# FPGA_GTX.net
KiCad netlist of a schematic drawn in Altium Designer
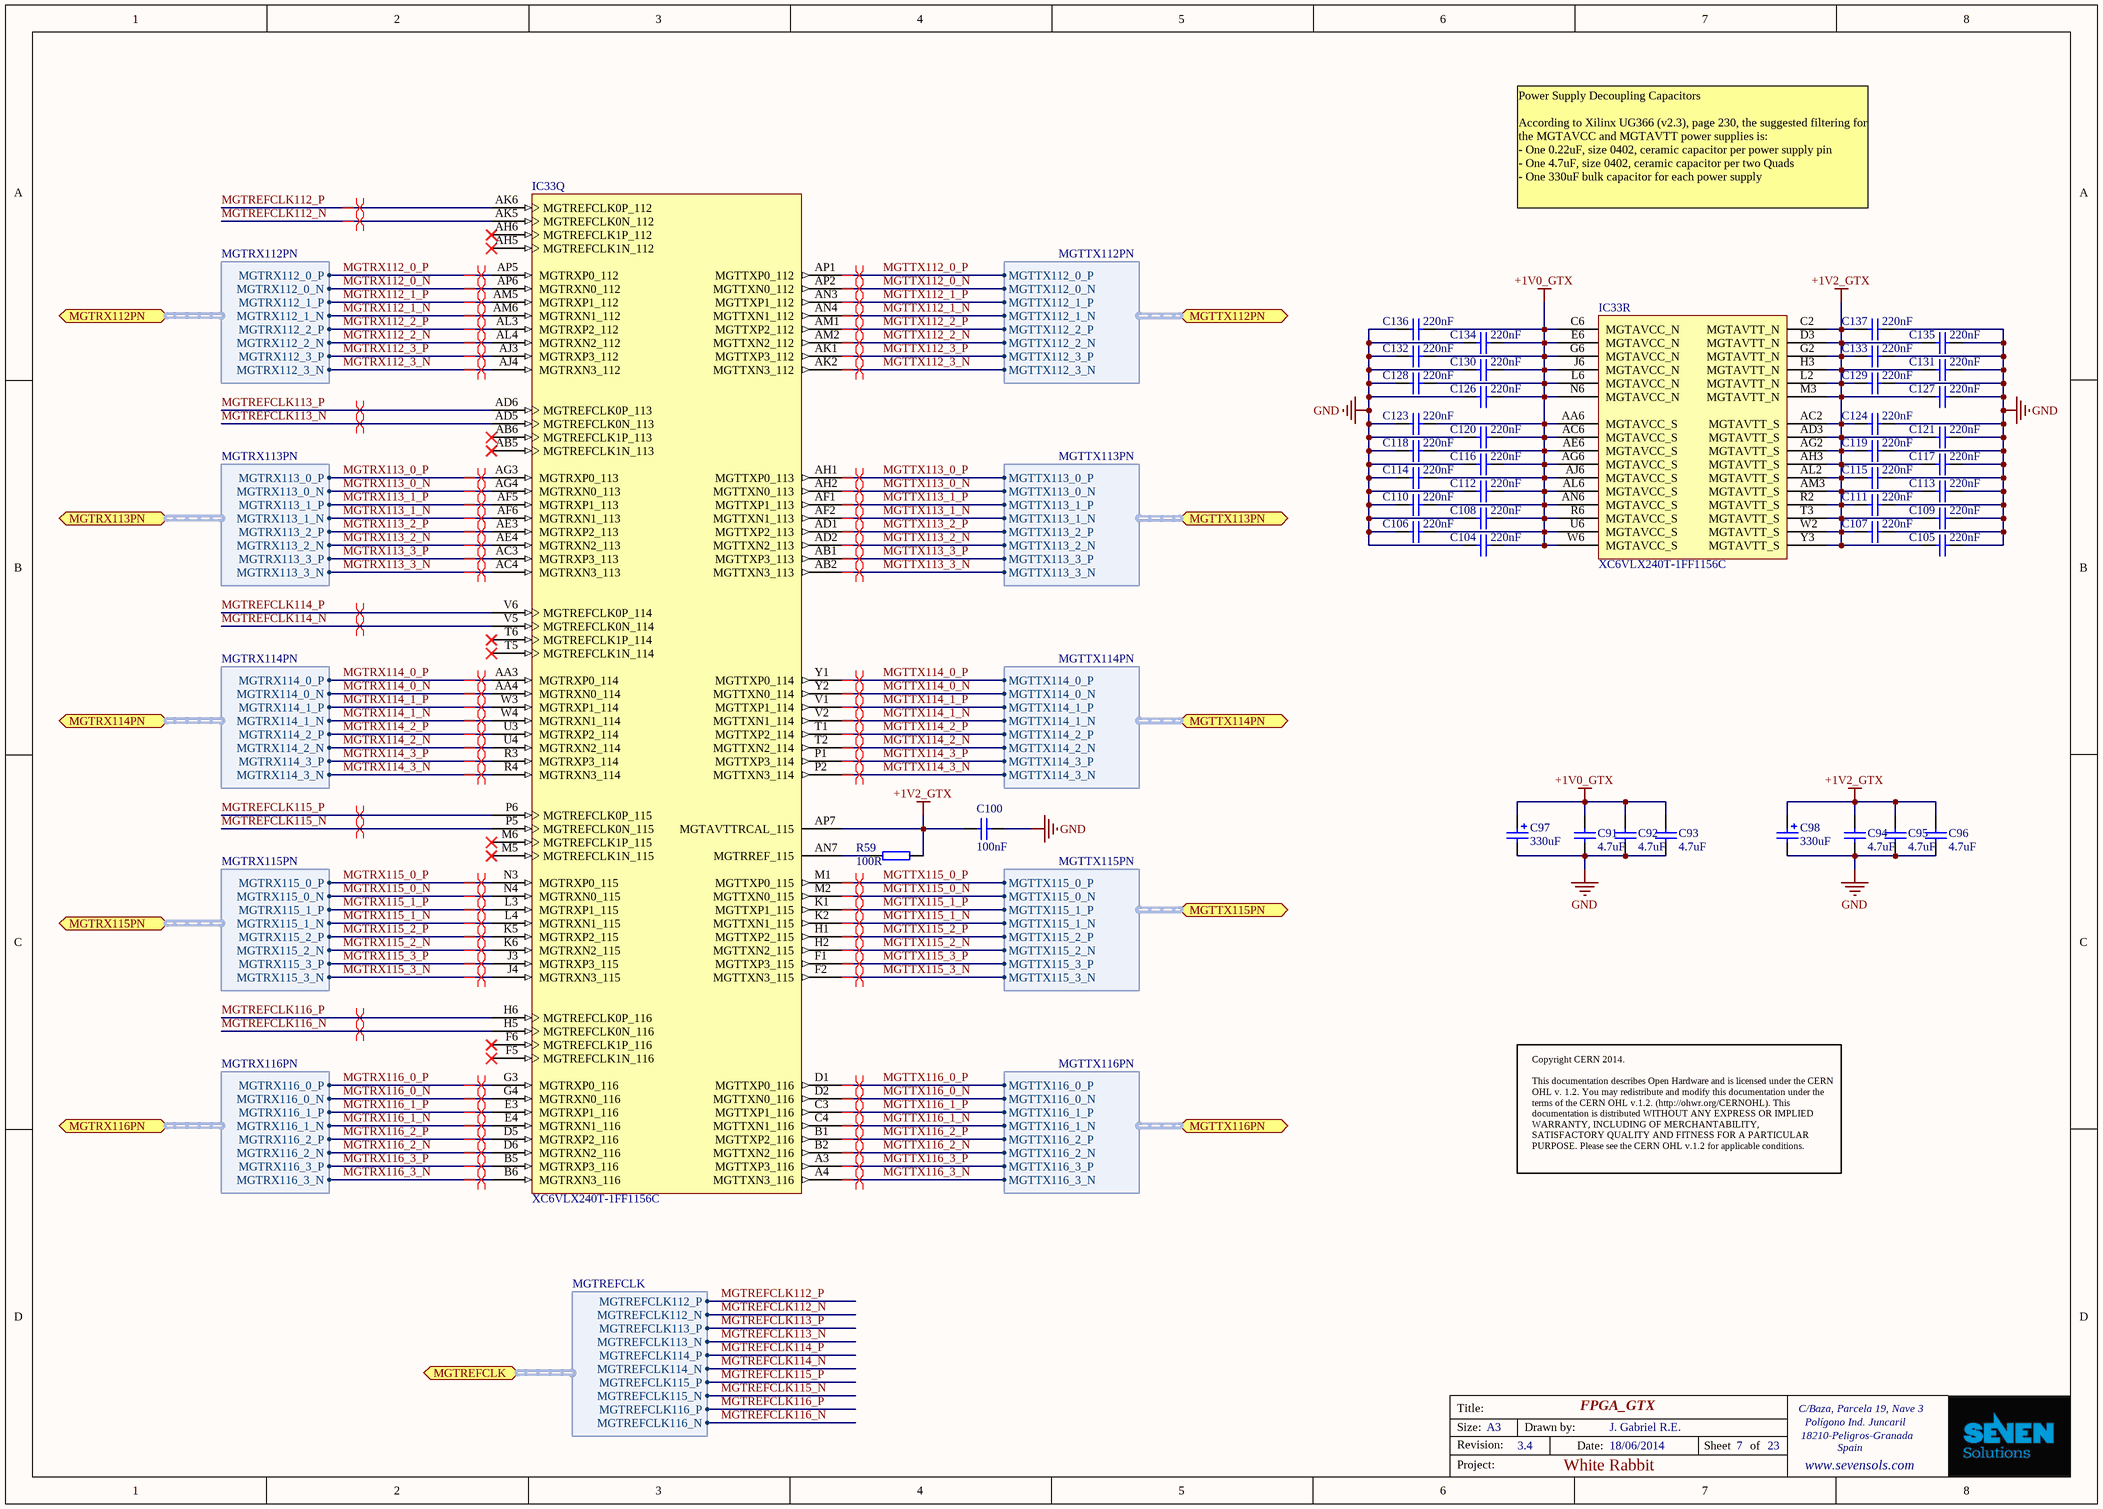
[diagram p0: FPGA_GTX.SchDoc]

(export (version "E")
  (design (tool "Eeschema 10.0.6"))
  (components
    (comp (ref "C91")
      (value "4.7uF")
      (footprint "CC1608-0603")
      (description "Capacitor")
      (fields
        (field (name "TOLERANCE") "±10%")
        (field (name "VOLTAGE") "10V")
        (field (name "PUBLISHER") "Altium Limited")
      )
      (libsource (lib "wr_switch") (part "Cap"))
    )
    (comp (ref "C92")
      (value "4.7uF")
      (footprint "CC1608-0603")
      (description "Capacitor")
      (fields
        (field (name "TOLERANCE") "±10%")
        (field (name "VOLTAGE") "10V")
        (field (name "PUBLISHER") "Altium Limited")
      )
      (libsource (lib "wr_switch") (part "Cap"))
    )
    (comp (ref "C93")
      (value "4.7uF")
      (footprint "CC1608-0603")
      (description "Capacitor")
      (fields
        (field (name "TOLERANCE") "±10%")
        (field (name "VOLTAGE") "10V")
        (field (name "PUBLISHER") "Altium Limited")
      )
      (libsource (lib "wr_switch") (part "Cap"))
    )
    (comp (ref "C94")
      (value "4.7uF")
      (footprint "CC1608-0603")
      (description "Capacitor")
      (fields
        (field (name "TOLERANCE") "±10%")
        (field (name "VOLTAGE") "10V")
        (field (name "PUBLISHER") "Altium Limited")
      )
      (libsource (lib "wr_switch") (part "Cap"))
    )
    (comp (ref "C95")
      (value "4.7uF")
      (footprint "CC1608-0603")
      (description "Capacitor")
      (fields
        (field (name "TOLERANCE") "±10%")
        (field (name "VOLTAGE") "10V")
        (field (name "PUBLISHER") "Altium Limited")
      )
      (libsource (lib "wr_switch") (part "Cap"))
    )
    (comp (ref "C96")
      (value "4.7uF")
      (footprint "CC1608-0603")
      (description "Capacitor")
      (fields
        (field (name "TOLERANCE") "±10%")
        (field (name "VOLTAGE") "10V")
        (field (name "PUBLISHER") "Altium Limited")
      )
      (libsource (lib "wr_switch") (part "Cap"))
    )
    (comp (ref "C97")
      (value "330uF")
      (footprint "D")
      (description "Polarized Capacitor Tantalum")
      (fields
        (field (name "TOLERANCE") "±20%")
        (field (name "VOLTAGE") "6.3V")
        (field (name "PUBLISHER") "Altium Limited")
      )
      (libsource (lib "wr_switch") (part "Cap Pol1"))
    )
    (comp (ref "C98")
      (value "330uF")
      (footprint "D")
      (description "Polarized Capacitor Tantalum")
      (fields
        (field (name "TOLERANCE") "±20%")
        (field (name "VOLTAGE") "6.3V")
        (field (name "PUBLISHER") "Altium Limited")
      )
      (libsource (lib "wr_switch") (part "Cap Pol1"))
    )
    (comp (ref "C100")
      (value "100nF")
      (footprint "CC1005-0402")
      (description "Capacitor")
      (fields
        (field (name "TOLERANCE") "±10%")
        (field (name "VOLTAGE") "16V")
        (field (name "PUBLISHER") "Altium Limited")
      )
      (libsource (lib "wr_switch") (part "Cap"))
    )
    (comp (ref "C104")
      (value "220nF")
      (footprint "CC1005-0402")
      (description "Capacitor")
      (fields
        (field (name "TOLERANCE") "±10%")
        (field (name "VOLTAGE") "16V")
        (field (name "PUBLISHER") "Altium Limited")
      )
      (libsource (lib "wr_switch") (part "Cap"))
    )
    (comp (ref "C105")
      (value "220nF")
      (footprint "CC1005-0402")
      (description "Capacitor")
      (fields
        (field (name "TOLERANCE") "±10%")
        (field (name "VOLTAGE") "16V")
        (field (name "PUBLISHER") "Altium Limited")
      )
      (libsource (lib "wr_switch") (part "Cap"))
    )
    (comp (ref "C106")
      (value "220nF")
      (footprint "CC1005-0402")
      (description "Capacitor")
      (fields
        (field (name "TOLERANCE") "±10%")
        (field (name "VOLTAGE") "16V")
        (field (name "PUBLISHER") "Altium Limited")
      )
      (libsource (lib "wr_switch") (part "Cap"))
    )
    (comp (ref "C107")
      (value "220nF")
      (footprint "CC1005-0402")
      (description "Capacitor")
      (fields
        (field (name "TOLERANCE") "±10%")
        (field (name "VOLTAGE") "16V")
        (field (name "PUBLISHER") "Altium Limited")
      )
      (libsource (lib "wr_switch") (part "Cap"))
    )
    (comp (ref "C108")
      (value "220nF")
      (footprint "CC1005-0402")
      (description "Capacitor")
      (fields
        (field (name "TOLERANCE") "±10%")
        (field (name "VOLTAGE") "16V")
        (field (name "PUBLISHER") "Altium Limited")
      )
      (libsource (lib "wr_switch") (part "Cap"))
    )
    (comp (ref "C109")
      (value "220nF")
      (footprint "CC1005-0402")
      (description "Capacitor")
      (fields
        (field (name "TOLERANCE") "±10%")
        (field (name "VOLTAGE") "16V")
        (field (name "PUBLISHER") "Altium Limited")
      )
      (libsource (lib "wr_switch") (part "Cap"))
    )
    (comp (ref "C110")
      (value "220nF")
      (footprint "CC1005-0402")
      (description "Capacitor")
      (fields
        (field (name "TOLERANCE") "±10%")
        (field (name "VOLTAGE") "16V")
        (field (name "PUBLISHER") "Altium Limited")
      )
      (libsource (lib "wr_switch") (part "Cap"))
    )
    (comp (ref "C111")
      (value "220nF")
      (footprint "CC1005-0402")
      (description "Capacitor")
      (fields
        (field (name "TOLERANCE") "±10%")
        (field (name "VOLTAGE") "16V")
        (field (name "PUBLISHER") "Altium Limited")
      )
      (libsource (lib "wr_switch") (part "Cap"))
    )
    (comp (ref "C112")
      (value "220nF")
      (footprint "CC1005-0402")
      (description "Capacitor")
      (fields
        (field (name "TOLERANCE") "±10%")
        (field (name "VOLTAGE") "16V")
        (field (name "PUBLISHER") "Altium Limited")
      )
      (libsource (lib "wr_switch") (part "Cap"))
    )
    (comp (ref "C113")
      (value "220nF")
      (footprint "CC1005-0402")
      (description "Capacitor")
      (fields
        (field (name "TOLERANCE") "±10%")
        (field (name "VOLTAGE") "16V")
        (field (name "PUBLISHER") "Altium Limited")
      )
      (libsource (lib "wr_switch") (part "Cap"))
    )
    (comp (ref "C114")
      (value "220nF")
      (footprint "CC1005-0402")
      (description "Capacitor")
      (fields
        (field (name "TOLERANCE") "±10%")
        (field (name "VOLTAGE") "16V")
        (field (name "PUBLISHER") "Altium Limited")
      )
      (libsource (lib "wr_switch") (part "Cap"))
    )
    (comp (ref "C115")
      (value "220nF")
      (footprint "CC1005-0402")
      (description "Capacitor")
      (fields
        (field (name "TOLERANCE") "±10%")
        (field (name "VOLTAGE") "16V")
        (field (name "PUBLISHER") "Altium Limited")
      )
      (libsource (lib "wr_switch") (part "Cap"))
    )
    (comp (ref "C116")
      (value "220nF")
      (footprint "CC1005-0402")
      (description "Capacitor")
      (fields
        (field (name "TOLERANCE") "±10%")
        (field (name "VOLTAGE") "16V")
        (field (name "PUBLISHER") "Altium Limited")
      )
      (libsource (lib "wr_switch") (part "Cap"))
    )
    (comp (ref "C117")
      (value "220nF")
      (footprint "CC1005-0402")
      (description "Capacitor")
      (fields
        (field (name "TOLERANCE") "±10%")
        (field (name "VOLTAGE") "16V")
        (field (name "PUBLISHER") "Altium Limited")
      )
      (libsource (lib "wr_switch") (part "Cap"))
    )
    (comp (ref "C118")
      (value "220nF")
      (footprint "CC1005-0402")
      (description "Capacitor")
      (fields
        (field (name "TOLERANCE") "±10%")
        (field (name "VOLTAGE") "16V")
        (field (name "PUBLISHER") "Altium Limited")
      )
      (libsource (lib "wr_switch") (part "Cap"))
    )
    (comp (ref "C119")
      (value "220nF")
      (footprint "CC1005-0402")
      (description "Capacitor")
      (fields
        (field (name "TOLERANCE") "±10%")
        (field (name "VOLTAGE") "16V")
        (field (name "PUBLISHER") "Altium Limited")
      )
      (libsource (lib "wr_switch") (part "Cap"))
    )
    (comp (ref "C120")
      (value "220nF")
      (footprint "CC1005-0402")
      (description "Capacitor")
      (fields
        (field (name "TOLERANCE") "±10%")
        (field (name "VOLTAGE") "16V")
        (field (name "PUBLISHER") "Altium Limited")
      )
      (libsource (lib "wr_switch") (part "Cap"))
    )
    (comp (ref "C121")
      (value "220nF")
      (footprint "CC1005-0402")
      (description "Capacitor")
      (fields
        (field (name "TOLERANCE") "±10%")
        (field (name "VOLTAGE") "16V")
        (field (name "PUBLISHER") "Altium Limited")
      )
      (libsource (lib "wr_switch") (part "Cap"))
    )
    (comp (ref "C123")
      (value "220nF")
      (footprint "CC1005-0402")
      (description "Capacitor")
      (fields
        (field (name "TOLERANCE") "±10%")
        (field (name "VOLTAGE") "16V")
        (field (name "PUBLISHER") "Altium Limited")
      )
      (libsource (lib "wr_switch") (part "Cap"))
    )
    (comp (ref "C124")
      (value "220nF")
      (footprint "CC1005-0402")
      (description "Capacitor")
      (fields
        (field (name "TOLERANCE") "±10%")
        (field (name "VOLTAGE") "16V")
        (field (name "PUBLISHER") "Altium Limited")
      )
      (libsource (lib "wr_switch") (part "Cap"))
    )
    (comp (ref "C126")
      (value "220nF")
      (footprint "CC1005-0402")
      (description "Capacitor")
      (fields
        (field (name "TOLERANCE") "±10%")
        (field (name "VOLTAGE") "16V")
        (field (name "PUBLISHER") "Altium Limited")
      )
      (libsource (lib "wr_switch") (part "Cap"))
    )
    (comp (ref "C127")
      (value "220nF")
      (footprint "CC1005-0402")
      (description "Capacitor")
      (fields
        (field (name "TOLERANCE") "±10%")
        (field (name "VOLTAGE") "16V")
        (field (name "PUBLISHER") "Altium Limited")
      )
      (libsource (lib "wr_switch") (part "Cap"))
    )
    (comp (ref "C128")
      (value "220nF")
      (footprint "CC1005-0402")
      (description "Capacitor")
      (fields
        (field (name "TOLERANCE") "±10%")
        (field (name "VOLTAGE") "16V")
        (field (name "PUBLISHER") "Altium Limited")
      )
      (libsource (lib "wr_switch") (part "Cap"))
    )
    (comp (ref "C129")
      (value "220nF")
      (footprint "CC1005-0402")
      (description "Capacitor")
      (fields
        (field (name "TOLERANCE") "±10%")
        (field (name "VOLTAGE") "16V")
        (field (name "PUBLISHER") "Altium Limited")
      )
      (libsource (lib "wr_switch") (part "Cap"))
    )
    (comp (ref "C130")
      (value "220nF")
      (footprint "CC1005-0402")
      (description "Capacitor")
      (fields
        (field (name "TOLERANCE") "±10%")
        (field (name "VOLTAGE") "16V")
        (field (name "PUBLISHER") "Altium Limited")
      )
      (libsource (lib "wr_switch") (part "Cap"))
    )
    (comp (ref "C131")
      (value "220nF")
      (footprint "CC1005-0402")
      (description "Capacitor")
      (fields
        (field (name "TOLERANCE") "±10%")
        (field (name "VOLTAGE") "16V")
        (field (name "PUBLISHER") "Altium Limited")
      )
      (libsource (lib "wr_switch") (part "Cap"))
    )
    (comp (ref "C132")
      (value "220nF")
      (footprint "CC1005-0402")
      (description "Capacitor")
      (fields
        (field (name "TOLERANCE") "±10%")
        (field (name "VOLTAGE") "16V")
        (field (name "PUBLISHER") "Altium Limited")
      )
      (libsource (lib "wr_switch") (part "Cap"))
    )
    (comp (ref "C133")
      (value "220nF")
      (footprint "CC1005-0402")
      (description "Capacitor")
      (fields
        (field (name "TOLERANCE") "±10%")
        (field (name "VOLTAGE") "16V")
        (field (name "PUBLISHER") "Altium Limited")
      )
      (libsource (lib "wr_switch") (part "Cap"))
    )
    (comp (ref "C134")
      (value "220nF")
      (footprint "CC1005-0402")
      (description "Capacitor")
      (fields
        (field (name "TOLERANCE") "±10%")
        (field (name "VOLTAGE") "16V")
        (field (name "PUBLISHER") "Altium Limited")
      )
      (libsource (lib "wr_switch") (part "Cap"))
    )
    (comp (ref "C135")
      (value "220nF")
      (footprint "CC1005-0402")
      (description "Capacitor")
      (fields
        (field (name "TOLERANCE") "±10%")
        (field (name "VOLTAGE") "16V")
        (field (name "PUBLISHER") "Altium Limited")
      )
      (libsource (lib "wr_switch") (part "Cap"))
    )
    (comp (ref "C136")
      (value "220nF")
      (footprint "CC1005-0402")
      (description "Capacitor")
      (fields
        (field (name "TOLERANCE") "±10%")
        (field (name "VOLTAGE") "16V")
        (field (name "PUBLISHER") "Altium Limited")
      )
      (libsource (lib "wr_switch") (part "Cap"))
    )
    (comp (ref "C137")
      (value "220nF")
      (footprint "CC1005-0402")
      (description "Capacitor")
      (fields
        (field (name "TOLERANCE") "±10%")
        (field (name "VOLTAGE") "16V")
        (field (name "PUBLISHER") "Altium Limited")
      )
      (libsource (lib "wr_switch") (part "Cap"))
    )
    (comp (ref "IC33")
      (value "XC6VLX240T-1FF1156C")
      (footprint "FF1156")
      (fields (field (name "PUBLISHER") "Altium Limited"))
      (libsource (lib "Xilinx Virtex-6") (part "XC6VLX240T-1FF1156C"))
    )
    (comp (ref "R59")
      (value "100R")
      (footprint "0402")
      (description "SMD Resistor")
      (fields (field (name "TOLERANCE") "±1%"))
      (libsource (lib "wr_switch") (part "RES_SMD"))
    )
  )
  (nets
    (net (code "12") (name "+1V0_GTX") (class "Default")
      (node (ref "C104") (pin "2") (pinfunction "2_2") (pintype "passive"))
      (node (ref "C106") (pin "2") (pinfunction "2_2") (pintype "passive"))
      (node (ref "C108") (pin "2") (pinfunction "2_2") (pintype "passive"))
      (node (ref "C110") (pin "2") (pinfunction "2_2") (pintype "passive"))
      (node (ref "C112") (pin "2") (pinfunction "2_2") (pintype "passive"))
      (node (ref "C114") (pin "2") (pinfunction "2_2") (pintype "passive"))
      (node (ref "C116") (pin "2") (pinfunction "2_2") (pintype "passive"))
      (node (ref "C118") (pin "2") (pinfunction "2_2") (pintype "passive"))
      (node (ref "C120") (pin "2") (pinfunction "2_2") (pintype "passive"))
      (node (ref "C123") (pin "2") (pinfunction "2_2") (pintype "passive"))
      (node (ref "C126") (pin "2") (pinfunction "2_2") (pintype "passive"))
      (node (ref "C128") (pin "2") (pinfunction "2_2") (pintype "passive"))
      (node (ref "C130") (pin "2") (pinfunction "2_2") (pintype "passive"))
      (node (ref "C132") (pin "2") (pinfunction "2_2") (pintype "passive"))
      (node (ref "C134") (pin "2") (pinfunction "2_2") (pintype "passive"))
      (node (ref "C136") (pin "2") (pinfunction "2_2") (pintype "passive"))
      (node (ref "C91") (pin "2") (pinfunction "2_2") (pintype "passive"))
      (node (ref "C92") (pin "2") (pinfunction "2_2") (pintype "passive"))
      (node (ref "C93") (pin "2") (pinfunction "2_2") (pintype "passive"))
      (node (ref "C97") (pin "1") (pinfunction "1_1") (pintype "passive"))
      (node (ref "IC33") (pin "AA6") (pinfunction "MGTAVCC_S_AA6") (pintype "power_in"))
      (node (ref "IC33") (pin "AC6") (pinfunction "MGTAVCC_S_AC6") (pintype "power_in"))
      (node (ref "IC33") (pin "AE6") (pinfunction "MGTAVCC_S_AE6") (pintype "power_in"))
      (node (ref "IC33") (pin "AG6") (pinfunction "MGTAVCC_S_AG6") (pintype "power_in"))
      (node (ref "IC33") (pin "AJ6") (pinfunction "MGTAVCC_S_AJ6") (pintype "power_in"))
      (node (ref "IC33") (pin "AL6") (pinfunction "MGTAVCC_S_AL6") (pintype "power_in"))
      (node (ref "IC33") (pin "AN6") (pinfunction "MGTAVCC_S_AN6") (pintype "power_in"))
      (node (ref "IC33") (pin "C6") (pinfunction "MGTAVCC_N_C6") (pintype "power_in"))
      (node (ref "IC33") (pin "E6") (pinfunction "MGTAVCC_N_E6") (pintype "power_in"))
      (node (ref "IC33") (pin "G6") (pinfunction "MGTAVCC_N_G6") (pintype "power_in"))
      (node (ref "IC33") (pin "J6") (pinfunction "MGTAVCC_N_J6") (pintype "power_in"))
      (node (ref "IC33") (pin "L6") (pinfunction "MGTAVCC_N_L6") (pintype "power_in"))
      (node (ref "IC33") (pin "N6") (pinfunction "MGTAVCC_N_N6") (pintype "power_in"))
      (node (ref "IC33") (pin "R6") (pinfunction "MGTAVCC_S_R6") (pintype "power_in"))
      (node (ref "IC33") (pin "U6") (pinfunction "MGTAVCC_S_U6") (pintype "power_in"))
      (node (ref "IC33") (pin "W6") (pinfunction "MGTAVCC_S_W6") (pintype "power_in"))
    )
    (net (code "13") (name "+1V2_GTX") (class "Default")
      (node (ref "C100") (pin "2") (pinfunction "2_2") (pintype "passive"))
      (node (ref "C105") (pin "1") (pinfunction "1_1") (pintype "passive"))
      (node (ref "C107") (pin "1") (pinfunction "1_1") (pintype "passive"))
      (node (ref "C109") (pin "1") (pinfunction "1_1") (pintype "passive"))
      (node (ref "C111") (pin "1") (pinfunction "1_1") (pintype "passive"))
      (node (ref "C113") (pin "1") (pinfunction "1_1") (pintype "passive"))
      (node (ref "C115") (pin "1") (pinfunction "1_1") (pintype "passive"))
      (node (ref "C117") (pin "1") (pinfunction "1_1") (pintype "passive"))
      (node (ref "C119") (pin "1") (pinfunction "1_1") (pintype "passive"))
      (node (ref "C121") (pin "1") (pinfunction "1_1") (pintype "passive"))
      (node (ref "C124") (pin "1") (pinfunction "1_1") (pintype "passive"))
      (node (ref "C127") (pin "1") (pinfunction "1_1") (pintype "passive"))
      (node (ref "C129") (pin "1") (pinfunction "1_1") (pintype "passive"))
      (node (ref "C131") (pin "1") (pinfunction "1_1") (pintype "passive"))
      (node (ref "C133") (pin "1") (pinfunction "1_1") (pintype "passive"))
      (node (ref "C135") (pin "1") (pinfunction "1_1") (pintype "passive"))
      (node (ref "C137") (pin "1") (pinfunction "1_1") (pintype "passive"))
      (node (ref "C94") (pin "2") (pinfunction "2_2") (pintype "passive"))
      (node (ref "C95") (pin "2") (pinfunction "2_2") (pintype "passive"))
      (node (ref "C96") (pin "2") (pinfunction "2_2") (pintype "passive"))
      (node (ref "C98") (pin "1") (pinfunction "1_1") (pintype "passive"))
      (node (ref "IC33") (pin "AC2") (pinfunction "MGTAVTT_S_AC2") (pintype "power_in"))
      (node (ref "IC33") (pin "AD3") (pinfunction "MGTAVTT_S_AD3") (pintype "power_in"))
      (node (ref "IC33") (pin "AG2") (pinfunction "MGTAVTT_S_AG2") (pintype "power_in"))
      (node (ref "IC33") (pin "AH3") (pinfunction "MGTAVTT_S_AH3") (pintype "power_in"))
      (node (ref "IC33") (pin "AL2") (pinfunction "MGTAVTT_S_AL2") (pintype "power_in"))
      (node (ref "IC33") (pin "AM3") (pinfunction "MGTAVTT_S_AM3") (pintype "power_in"))
      (node (ref "IC33") (pin "AP7") (pinfunction "MGTAVTTRCAL_115_AP7") (pintype "passive"))
      (node (ref "IC33") (pin "C2") (pinfunction "MGTAVTT_N_C2") (pintype "power_in"))
      (node (ref "IC33") (pin "D3") (pinfunction "MGTAVTT_N_D3") (pintype "power_in"))
      (node (ref "IC33") (pin "G2") (pinfunction "MGTAVTT_N_G2") (pintype "power_in"))
      (node (ref "IC33") (pin "H3") (pinfunction "MGTAVTT_N_H3") (pintype "power_in"))
      (node (ref "IC33") (pin "L2") (pinfunction "MGTAVTT_N_L2") (pintype "power_in"))
      (node (ref "IC33") (pin "M3") (pinfunction "MGTAVTT_N_M3") (pintype "power_in"))
      (node (ref "IC33") (pin "R2") (pinfunction "MGTAVTT_S_R2") (pintype "power_in"))
      (node (ref "IC33") (pin "T3") (pinfunction "MGTAVTT_S_T3") (pintype "power_in"))
      (node (ref "IC33") (pin "W2") (pinfunction "MGTAVTT_S_W2") (pintype "power_in"))
      (node (ref "IC33") (pin "Y3") (pinfunction "MGTAVTT_S_Y3") (pintype "power_in"))
      (node (ref "R59") (pin "1") (pinfunction "1_1") (pintype "passive"))
    )
    (net (code "14") (name "/MGTREFCLK112_N") (class "Default")
      (node (ref "IC33") (pin "AK5") (pinfunction "MGTREFCLK0N_112_AK5") (pintype "input"))
    )
    (net (code "15") (name "/MGTREFCLK112_P") (class "Default")
      (node (ref "IC33") (pin "AK6") (pinfunction "MGTREFCLK0P_112_AK6") (pintype "input"))
    )
    (net (code "16") (name "/MGTREFCLK113_N") (class "Default")
      (node (ref "IC33") (pin "AD5") (pinfunction "MGTREFCLK0N_113_AD5") (pintype "input"))
    )
    (net (code "17") (name "/MGTREFCLK113_P") (class "Default")
      (node (ref "IC33") (pin "AD6") (pinfunction "MGTREFCLK0P_113_AD6") (pintype "input"))
    )
    (net (code "18") (name "/MGTREFCLK114_N") (class "Default")
      (node (ref "IC33") (pin "V5") (pinfunction "MGTREFCLK0N_114_V5") (pintype "input"))
    )
    (net (code "19") (name "/MGTREFCLK114_P") (class "Default")
      (node (ref "IC33") (pin "V6") (pinfunction "MGTREFCLK0P_114_V6") (pintype "input"))
    )
    (net (code "20") (name "/MGTREFCLK115_N") (class "Default")
      (node (ref "IC33") (pin "P5") (pinfunction "MGTREFCLK0N_115_P5") (pintype "input"))
    )
    (net (code "21") (name "/MGTREFCLK115_P") (class "Default")
      (node (ref "IC33") (pin "P6") (pinfunction "MGTREFCLK0P_115_P6") (pintype "input"))
    )
    (net (code "22") (name "/MGTREFCLK116_N") (class "Default")
      (node (ref "IC33") (pin "H5") (pinfunction "MGTREFCLK0N_116_H5") (pintype "input"))
    )
    (net (code "23") (name "/MGTREFCLK116_P") (class "Default")
      (node (ref "IC33") (pin "H6") (pinfunction "MGTREFCLK0P_116_H6") (pintype "input"))
    )
    (net (code "24") (name "/MGTRX112_0_N") (class "Default")
      (node (ref "IC33") (pin "AP6") (pinfunction "MGTRXN0_112_AP6") (pintype "input"))
    )
    (net (code "25") (name "/MGTRX112_0_P") (class "Default")
      (node (ref "IC33") (pin "AP5") (pinfunction "MGTRXP0_112_AP5") (pintype "input"))
    )
    (net (code "26") (name "/MGTRX112_1_N") (class "Default")
      (node (ref "IC33") (pin "AM6") (pinfunction "MGTRXN1_112_AM6") (pintype "input"))
    )
    (net (code "27") (name "/MGTRX112_1_P") (class "Default")
      (node (ref "IC33") (pin "AM5") (pinfunction "MGTRXP1_112_AM5") (pintype "input"))
    )
    (net (code "28") (name "/MGTRX112_2_N") (class "Default")
      (node (ref "IC33") (pin "AL4") (pinfunction "MGTRXN2_112_AL4") (pintype "input"))
    )
    (net (code "29") (name "/MGTRX112_2_P") (class "Default")
      (node (ref "IC33") (pin "AL3") (pinfunction "MGTRXP2_112_AL3") (pintype "input"))
    )
    (net (code "30") (name "/MGTRX112_3_N") (class "Default")
      (node (ref "IC33") (pin "AJ4") (pinfunction "MGTRXN3_112_AJ4") (pintype "input"))
    )
    (net (code "31") (name "/MGTRX112_3_P") (class "Default")
      (node (ref "IC33") (pin "AJ3") (pinfunction "MGTRXP3_112_AJ3") (pintype "input"))
    )
    (net (code "32") (name "/MGTRX113_0_N") (class "Default")
      (node (ref "IC33") (pin "AG4") (pinfunction "MGTRXN0_113_AG4") (pintype "input"))
    )
    (net (code "33") (name "/MGTRX113_0_P") (class "Default")
      (node (ref "IC33") (pin "AG3") (pinfunction "MGTRXP0_113_AG3") (pintype "input"))
    )
    (net (code "34") (name "/MGTRX113_1_N") (class "Default")
      (node (ref "IC33") (pin "AF6") (pinfunction "MGTRXN1_113_AF6") (pintype "input"))
    )
    (net (code "35") (name "/MGTRX113_1_P") (class "Default")
      (node (ref "IC33") (pin "AF5") (pinfunction "MGTRXP1_113_AF5") (pintype "input"))
    )
    (net (code "36") (name "/MGTRX113_2_N") (class "Default")
      (node (ref "IC33") (pin "AE4") (pinfunction "MGTRXN2_113_AE4") (pintype "input"))
    )
    (net (code "37") (name "/MGTRX113_2_P") (class "Default")
      (node (ref "IC33") (pin "AE3") (pinfunction "MGTRXP2_113_AE3") (pintype "input"))
    )
    (net (code "38") (name "/MGTRX113_3_N") (class "Default")
      (node (ref "IC33") (pin "AC4") (pinfunction "MGTRXN3_113_AC4") (pintype "input"))
    )
    (net (code "39") (name "/MGTRX113_3_P") (class "Default")
      (node (ref "IC33") (pin "AC3") (pinfunction "MGTRXP3_113_AC3") (pintype "input"))
    )
    (net (code "40") (name "/MGTRX114_0_N") (class "Default")
      (node (ref "IC33") (pin "AA4") (pinfunction "MGTRXN0_114_AA4") (pintype "input"))
    )
    (net (code "41") (name "/MGTRX114_0_P") (class "Default")
      (node (ref "IC33") (pin "AA3") (pinfunction "MGTRXP0_114_AA3") (pintype "input"))
    )
    (net (code "42") (name "/MGTRX114_1_N") (class "Default")
      (node (ref "IC33") (pin "W4") (pinfunction "MGTRXN1_114_W4") (pintype "input"))
    )
    (net (code "43") (name "/MGTRX114_1_P") (class "Default")
      (node (ref "IC33") (pin "W3") (pinfunction "MGTRXP1_114_W3") (pintype "input"))
    )
    (net (code "44") (name "/MGTRX114_2_N") (class "Default")
      (node (ref "IC33") (pin "U4") (pinfunction "MGTRXN2_114_U4") (pintype "input"))
    )
    (net (code "45") (name "/MGTRX114_2_P") (class "Default")
      (node (ref "IC33") (pin "U3") (pinfunction "MGTRXP2_114_U3") (pintype "input"))
    )
    (net (code "46") (name "/MGTRX114_3_N") (class "Default")
      (node (ref "IC33") (pin "R4") (pinfunction "MGTRXN3_114_R4") (pintype "input"))
    )
    (net (code "47") (name "/MGTRX114_3_P") (class "Default")
      (node (ref "IC33") (pin "R3") (pinfunction "MGTRXP3_114_R3") (pintype "input"))
    )
    (net (code "48") (name "/MGTRX115_0_N") (class "Default")
      (node (ref "IC33") (pin "N4") (pinfunction "MGTRXN0_115_N4") (pintype "input"))
    )
    (net (code "49") (name "/MGTRX115_0_P") (class "Default")
      (node (ref "IC33") (pin "N3") (pinfunction "MGTRXP0_115_N3") (pintype "input"))
    )
    (net (code "50") (name "/MGTRX115_1_N") (class "Default")
      (node (ref "IC33") (pin "L4") (pinfunction "MGTRXN1_115_L4") (pintype "input"))
    )
    (net (code "51") (name "/MGTRX115_1_P") (class "Default")
      (node (ref "IC33") (pin "L3") (pinfunction "MGTRXP1_115_L3") (pintype "input"))
    )
    (net (code "52") (name "/MGTRX115_2_N") (class "Default")
      (node (ref "IC33") (pin "K6") (pinfunction "MGTRXN2_115_K6") (pintype "input"))
    )
    (net (code "53") (name "/MGTRX115_2_P") (class "Default")
      (node (ref "IC33") (pin "K5") (pinfunction "MGTRXP2_115_K5") (pintype "input"))
    )
    (net (code "54") (name "/MGTRX115_3_N") (class "Default")
      (node (ref "IC33") (pin "J4") (pinfunction "MGTRXN3_115_J4") (pintype "input"))
    )
    (net (code "55") (name "/MGTRX115_3_P") (class "Default")
      (node (ref "IC33") (pin "J3") (pinfunction "MGTRXP3_115_J3") (pintype "input"))
    )
    (net (code "56") (name "/MGTRX116_0_N") (class "Default")
      (node (ref "IC33") (pin "G4") (pinfunction "MGTRXN0_116_G4") (pintype "input"))
    )
    (net (code "57") (name "/MGTRX116_0_P") (class "Default")
      (node (ref "IC33") (pin "G3") (pinfunction "MGTRXP0_116_G3") (pintype "input"))
    )
    (net (code "58") (name "/MGTRX116_1_N") (class "Default")
      (node (ref "IC33") (pin "E4") (pinfunction "MGTRXN1_116_E4") (pintype "input"))
    )
    (net (code "59") (name "/MGTRX116_1_P") (class "Default")
      (node (ref "IC33") (pin "E3") (pinfunction "MGTRXP1_116_E3") (pintype "input"))
    )
    (net (code "60") (name "/MGTRX116_2_N") (class "Default")
      (node (ref "IC33") (pin "D6") (pinfunction "MGTRXN2_116_D6") (pintype "input"))
    )
    (net (code "61") (name "/MGTRX116_2_P") (class "Default")
      (node (ref "IC33") (pin "D5") (pinfunction "MGTRXP2_116_D5") (pintype "input"))
    )
    (net (code "62") (name "/MGTRX116_3_N") (class "Default")
      (node (ref "IC33") (pin "B6") (pinfunction "MGTRXN3_116_B6") (pintype "input"))
    )
    (net (code "63") (name "/MGTRX116_3_P") (class "Default")
      (node (ref "IC33") (pin "B5") (pinfunction "MGTRXP3_116_B5") (pintype "input"))
    )
    (net (code "64") (name "/MGTTX112_0_N") (class "Default")
      (node (ref "IC33") (pin "AP2") (pinfunction "MGTTXN0_112_AP2") (pintype "output"))
    )
    (net (code "65") (name "/MGTTX112_0_P") (class "Default")
      (node (ref "IC33") (pin "AP1") (pinfunction "MGTTXP0_112_AP1") (pintype "output"))
    )
    (net (code "66") (name "/MGTTX112_1_N") (class "Default")
      (node (ref "IC33") (pin "AN4") (pinfunction "MGTTXN1_112_AN4") (pintype "output"))
    )
    (net (code "67") (name "/MGTTX112_1_P") (class "Default")
      (node (ref "IC33") (pin "AN3") (pinfunction "MGTTXP1_112_AN3") (pintype "output"))
    )
    (net (code "68") (name "/MGTTX112_2_N") (class "Default")
      (node (ref "IC33") (pin "AM2") (pinfunction "MGTTXN2_112_AM2") (pintype "output"))
    )
    (net (code "69") (name "/MGTTX112_2_P") (class "Default")
      (node (ref "IC33") (pin "AM1") (pinfunction "MGTTXP2_112_AM1") (pintype "output"))
    )
    (net (code "70") (name "/MGTTX112_3_N") (class "Default")
      (node (ref "IC33") (pin "AK2") (pinfunction "MGTTXN3_112_AK2") (pintype "output"))
    )
    (net (code "71") (name "/MGTTX112_3_P") (class "Default")
      (node (ref "IC33") (pin "AK1") (pinfunction "MGTTXP3_112_AK1") (pintype "output"))
    )
    (net (code "72") (name "/MGTTX113_0_N") (class "Default")
      (node (ref "IC33") (pin "AH2") (pinfunction "MGTTXN0_113_AH2") (pintype "output"))
    )
    (net (code "73") (name "/MGTTX113_0_P") (class "Default")
      (node (ref "IC33") (pin "AH1") (pinfunction "MGTTXP0_113_AH1") (pintype "output"))
    )
    (net (code "74") (name "/MGTTX113_1_N") (class "Default")
      (node (ref "IC33") (pin "AF2") (pinfunction "MGTTXN1_113_AF2") (pintype "output"))
    )
    (net (code "75") (name "/MGTTX113_1_P") (class "Default")
      (node (ref "IC33") (pin "AF1") (pinfunction "MGTTXP1_113_AF1") (pintype "output"))
    )
    (net (code "76") (name "/MGTTX113_2_N") (class "Default")
      (node (ref "IC33") (pin "AD2") (pinfunction "MGTTXN2_113_AD2") (pintype "output"))
    )
    (net (code "77") (name "/MGTTX113_2_P") (class "Default")
      (node (ref "IC33") (pin "AD1") (pinfunction "MGTTXP2_113_AD1") (pintype "output"))
    )
    (net (code "78") (name "/MGTTX113_3_N") (class "Default")
      (node (ref "IC33") (pin "AB2") (pinfunction "MGTTXN3_113_AB2") (pintype "output"))
    )
    (net (code "79") (name "/MGTTX113_3_P") (class "Default")
      (node (ref "IC33") (pin "AB1") (pinfunction "MGTTXP3_113_AB1") (pintype "output"))
    )
    (net (code "80") (name "/MGTTX114_0_N") (class "Default")
      (node (ref "IC33") (pin "Y2") (pinfunction "MGTTXN0_114_Y2") (pintype "output"))
    )
    (net (code "81") (name "/MGTTX114_0_P") (class "Default")
      (node (ref "IC33") (pin "Y1") (pinfunction "MGTTXP0_114_Y1") (pintype "output"))
    )
    (net (code "82") (name "/MGTTX114_1_N") (class "Default")
      (node (ref "IC33") (pin "V2") (pinfunction "MGTTXN1_114_V2") (pintype "output"))
    )
    (net (code "83") (name "/MGTTX114_1_P") (class "Default")
      (node (ref "IC33") (pin "V1") (pinfunction "MGTTXP1_114_V1") (pintype "output"))
    )
    (net (code "84") (name "/MGTTX114_2_N") (class "Default")
      (node (ref "IC33") (pin "T2") (pinfunction "MGTTXN2_114_T2") (pintype "output"))
    )
    (net (code "85") (name "/MGTTX114_2_P") (class "Default")
      (node (ref "IC33") (pin "T1") (pinfunction "MGTTXP2_114_T1") (pintype "output"))
    )
    (net (code "86") (name "/MGTTX114_3_N") (class "Default")
      (node (ref "IC33") (pin "P2") (pinfunction "MGTTXN3_114_P2") (pintype "output"))
    )
    (net (code "87") (name "/MGTTX114_3_P") (class "Default")
      (node (ref "IC33") (pin "P1") (pinfunction "MGTTXP3_114_P1") (pintype "output"))
    )
    (net (code "88") (name "/MGTTX115_0_N") (class "Default")
      (node (ref "IC33") (pin "M2") (pinfunction "MGTTXN0_115_M2") (pintype "output"))
    )
    (net (code "89") (name "/MGTTX115_0_P") (class "Default")
      (node (ref "IC33") (pin "M1") (pinfunction "MGTTXP0_115_M1") (pintype "output"))
    )
    (net (code "90") (name "/MGTTX115_1_N") (class "Default")
      (node (ref "IC33") (pin "K2") (pinfunction "MGTTXN1_115_K2") (pintype "output"))
    )
    (net (code "91") (name "/MGTTX115_1_P") (class "Default")
      (node (ref "IC33") (pin "K1") (pinfunction "MGTTXP1_115_K1") (pintype "output"))
    )
    (net (code "92") (name "/MGTTX115_2_N") (class "Default")
      (node (ref "IC33") (pin "H2") (pinfunction "MGTTXN2_115_H2") (pintype "output"))
    )
    (net (code "93") (name "/MGTTX115_2_P") (class "Default")
      (node (ref "IC33") (pin "H1") (pinfunction "MGTTXP2_115_H1") (pintype "output"))
    )
    (net (code "94") (name "/MGTTX115_3_N") (class "Default")
      (node (ref "IC33") (pin "F2") (pinfunction "MGTTXN3_115_F2") (pintype "output"))
    )
    (net (code "95") (name "/MGTTX115_3_P") (class "Default")
      (node (ref "IC33") (pin "F1") (pinfunction "MGTTXP3_115_F1") (pintype "output"))
    )
    (net (code "96") (name "/MGTTX116_0_N") (class "Default")
      (node (ref "IC33") (pin "D2") (pinfunction "MGTTXN0_116_D2") (pintype "output"))
    )
    (net (code "97") (name "/MGTTX116_0_P") (class "Default")
      (node (ref "IC33") (pin "D1") (pinfunction "MGTTXP0_116_D1") (pintype "output"))
    )
    (net (code "98") (name "/MGTTX116_1_N") (class "Default")
      (node (ref "IC33") (pin "C4") (pinfunction "MGTTXN1_116_C4") (pintype "output"))
    )
    (net (code "99") (name "/MGTTX116_1_P") (class "Default")
      (node (ref "IC33") (pin "C3") (pinfunction "MGTTXP1_116_C3") (pintype "output"))
    )
    (net (code "100") (name "/MGTTX116_2_N") (class "Default")
      (node (ref "IC33") (pin "B2") (pinfunction "MGTTXN2_116_B2") (pintype "output"))
    )
    (net (code "101") (name "/MGTTX116_2_P") (class "Default")
      (node (ref "IC33") (pin "B1") (pinfunction "MGTTXP2_116_B1") (pintype "output"))
    )
    (net (code "102") (name "/MGTTX116_3_N") (class "Default")
      (node (ref "IC33") (pin "A4") (pinfunction "MGTTXN3_116_A4") (pintype "output"))
    )
    (net (code "103") (name "/MGTTX116_3_P") (class "Default")
      (node (ref "IC33") (pin "A3") (pinfunction "MGTTXP3_116_A3") (pintype "output"))
    )
    (net (code "115") (name "GND") (class "Default")
      (node (ref "C100") (pin "1") (pinfunction "1_1") (pintype "passive"))
      (node (ref "C104") (pin "1") (pinfunction "1_1") (pintype "passive"))
      (node (ref "C105") (pin "2") (pinfunction "2_2") (pintype "passive"))
      (node (ref "C106") (pin "1") (pinfunction "1_1") (pintype "passive"))
      (node (ref "C107") (pin "2") (pinfunction "2_2") (pintype "passive"))
      (node (ref "C108") (pin "1") (pinfunction "1_1") (pintype "passive"))
      (node (ref "C109") (pin "2") (pinfunction "2_2") (pintype "passive"))
      (node (ref "C110") (pin "1") (pinfunction "1_1") (pintype "passive"))
      (node (ref "C111") (pin "2") (pinfunction "2_2") (pintype "passive"))
      (node (ref "C112") (pin "1") (pinfunction "1_1") (pintype "passive"))
      (node (ref "C113") (pin "2") (pinfunction "2_2") (pintype "passive"))
      (node (ref "C114") (pin "1") (pinfunction "1_1") (pintype "passive"))
      (node (ref "C115") (pin "2") (pinfunction "2_2") (pintype "passive"))
      (node (ref "C116") (pin "1") (pinfunction "1_1") (pintype "passive"))
      (node (ref "C117") (pin "2") (pinfunction "2_2") (pintype "passive"))
      (node (ref "C118") (pin "1") (pinfunction "1_1") (pintype "passive"))
      (node (ref "C119") (pin "2") (pinfunction "2_2") (pintype "passive"))
      (node (ref "C120") (pin "1") (pinfunction "1_1") (pintype "passive"))
      (node (ref "C121") (pin "2") (pinfunction "2_2") (pintype "passive"))
      (node (ref "C123") (pin "1") (pinfunction "1_1") (pintype "passive"))
      (node (ref "C124") (pin "2") (pinfunction "2_2") (pintype "passive"))
      (node (ref "C126") (pin "1") (pinfunction "1_1") (pintype "passive"))
      (node (ref "C127") (pin "2") (pinfunction "2_2") (pintype "passive"))
      (node (ref "C128") (pin "1") (pinfunction "1_1") (pintype "passive"))
      (node (ref "C129") (pin "2") (pinfunction "2_2") (pintype "passive"))
      (node (ref "C130") (pin "1") (pinfunction "1_1") (pintype "passive"))
      (node (ref "C131") (pin "2") (pinfunction "2_2") (pintype "passive"))
      (node (ref "C132") (pin "1") (pinfunction "1_1") (pintype "passive"))
      (node (ref "C133") (pin "2") (pinfunction "2_2") (pintype "passive"))
      (node (ref "C134") (pin "1") (pinfunction "1_1") (pintype "passive"))
      (node (ref "C135") (pin "2") (pinfunction "2_2") (pintype "passive"))
      (node (ref "C136") (pin "1") (pinfunction "1_1") (pintype "passive"))
      (node (ref "C137") (pin "2") (pinfunction "2_2") (pintype "passive"))
      (node (ref "C91") (pin "1") (pinfunction "1_1") (pintype "passive"))
      (node (ref "C92") (pin "1") (pinfunction "1_1") (pintype "passive"))
      (node (ref "C93") (pin "1") (pinfunction "1_1") (pintype "passive"))
      (node (ref "C94") (pin "1") (pinfunction "1_1") (pintype "passive"))
      (node (ref "C95") (pin "1") (pinfunction "1_1") (pintype "passive"))
      (node (ref "C96") (pin "1") (pinfunction "1_1") (pintype "passive"))
      (node (ref "C97") (pin "2") (pinfunction "2_2") (pintype "passive"))
      (node (ref "C98") (pin "2") (pinfunction "2_2") (pintype "passive"))
    )
    (net (code "116") (name "Net-(IC33Q-MGTRREF_115)") (class "Default")
      (node (ref "IC33") (pin "AN7") (pinfunction "MGTRREF_115_AN7") (pintype "passive"))
      (node (ref "R59") (pin "2") (pinfunction "2_2") (pintype "passive"))
    )
    (net (code "117") (name "unconnected-(IC33Q-MGTREFCLK1N_112-PadAH5)") (class "Default")
      (node (ref "IC33") (pin "AH5") (pinfunction "MGTREFCLK1N_112_AH5") (pintype "input+no_connect"))
    )
    (net (code "118") (name "unconnected-(IC33Q-MGTREFCLK1N_113-PadAB5)") (class "Default")
      (node (ref "IC33") (pin "AB5") (pinfunction "MGTREFCLK1N_113_AB5") (pintype "input+no_connect"))
    )
    (net (code "119") (name "unconnected-(IC33Q-MGTREFCLK1N_114-PadT5)") (class "Default")
      (node (ref "IC33") (pin "T5") (pinfunction "MGTREFCLK1N_114_T5") (pintype "input+no_connect"))
    )
    (net (code "120") (name "unconnected-(IC33Q-MGTREFCLK1N_115-PadM5)") (class "Default")
      (node (ref "IC33") (pin "M5") (pinfunction "MGTREFCLK1N_115_M5") (pintype "input+no_connect"))
    )
    (net (code "121") (name "unconnected-(IC33Q-MGTREFCLK1N_116-PadF5)") (class "Default")
      (node (ref "IC33") (pin "F5") (pinfunction "MGTREFCLK1N_116_F5") (pintype "input+no_connect"))
    )
    (net (code "122") (name "unconnected-(IC33Q-MGTREFCLK1P_112-PadAH6)") (class "Default")
      (node (ref "IC33") (pin "AH6") (pinfunction "MGTREFCLK1P_112_AH6") (pintype "input+no_connect"))
    )
    (net (code "123") (name "unconnected-(IC33Q-MGTREFCLK1P_113-PadAB6)") (class "Default")
      (node (ref "IC33") (pin "AB6") (pinfunction "MGTREFCLK1P_113_AB6") (pintype "input+no_connect"))
    )
    (net (code "124") (name "unconnected-(IC33Q-MGTREFCLK1P_114-PadT6)") (class "Default")
      (node (ref "IC33") (pin "T6") (pinfunction "MGTREFCLK1P_114_T6") (pintype "input+no_connect"))
    )
    (net (code "125") (name "unconnected-(IC33Q-MGTREFCLK1P_115-PadM6)") (class "Default")
      (node (ref "IC33") (pin "M6") (pinfunction "MGTREFCLK1P_115_M6") (pintype "input+no_connect"))
    )
    (net (code "126") (name "unconnected-(IC33Q-MGTREFCLK1P_116-PadF6)") (class "Default")
      (node (ref "IC33") (pin "F6") (pinfunction "MGTREFCLK1P_116_F6") (pintype "input+no_connect"))
    )
  )
)
